# PhaseCLeg.net
KiCad netlist of a schematic drawn in Altium Designer
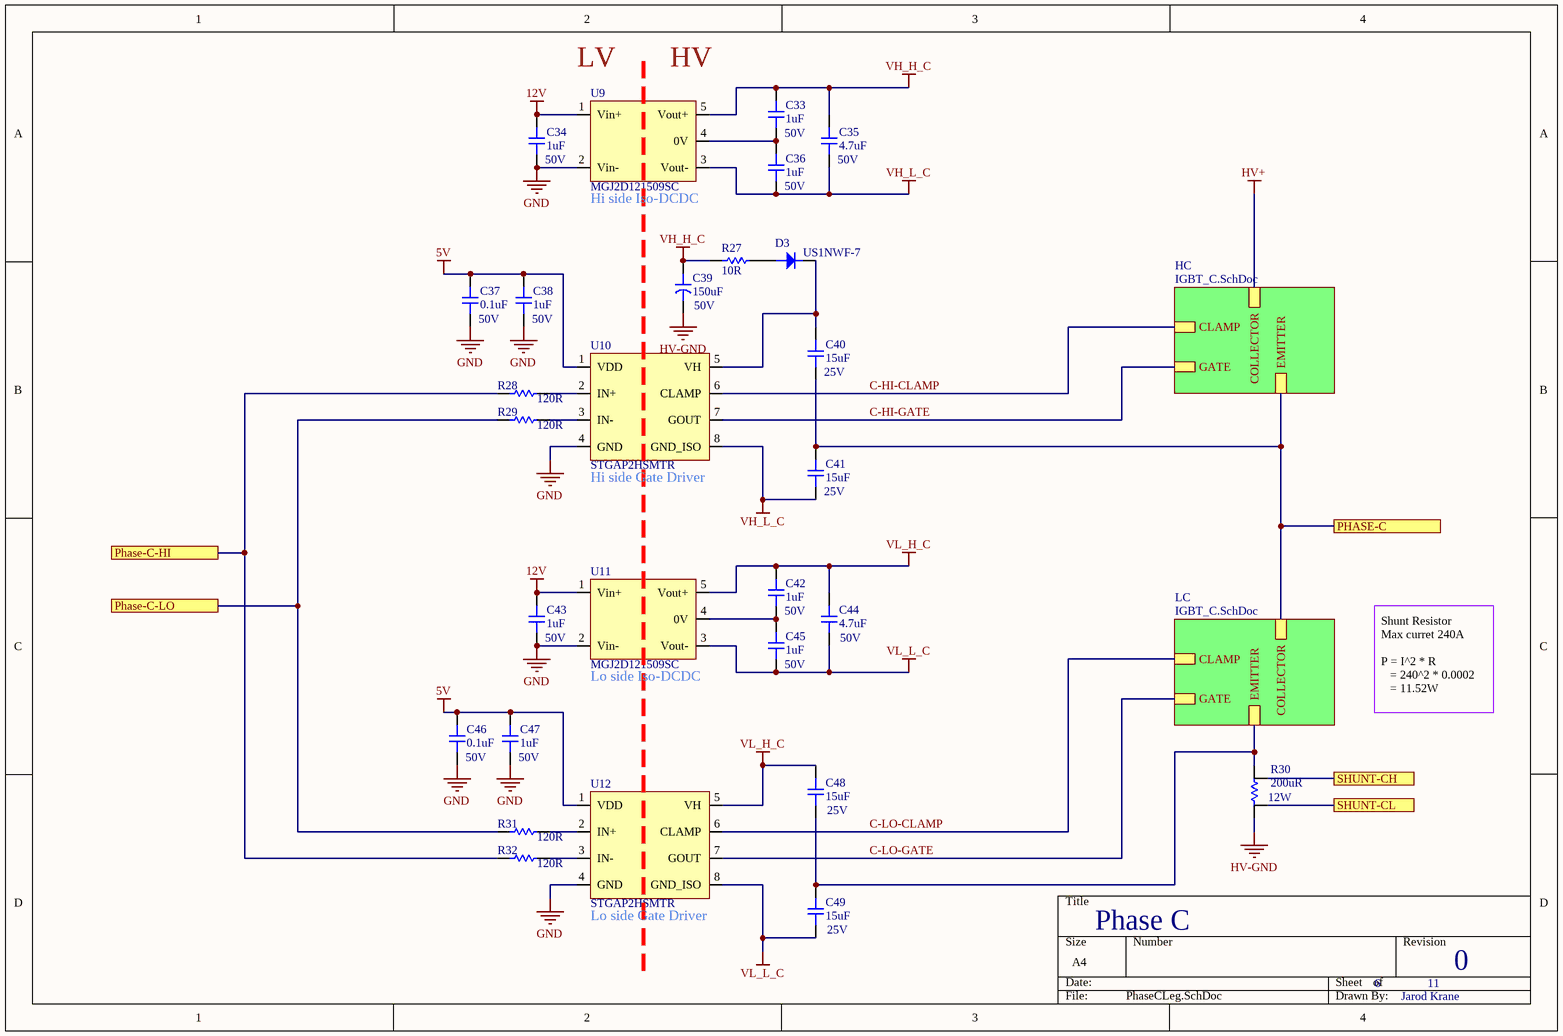
[diagram p0: PhaseCLeg.SchDoc]

(export (version "E")
  (design (tool "Eeschema 10.0.6"))
  (components
    (comp (ref "C33")
      (value "1uF")
      (footprint "CAP-0805")
      (description "CAP CER 1UF 50V X5R 0805")
      (fields
        (field (name "MANUFACTURER") "KEMET")
        (field (name "MANUFACTURER PART NUMBER") "C0805C105K5PACTU")
        (field (name "VOLTAGE RATING") "50V")
      )
      (libsource (lib "InverterSCHLib") (part "0805-1uF-50V"))
    )
    (comp (ref "C34")
      (value "1uF")
      (footprint "CAP-0805")
      (description "CAP CER 1UF 50V X5R 0805")
      (fields
        (field (name "MANUFACTURER") "KEMET")
        (field (name "MANUFACTURER PART NUMBER") "C0805C105K5PACTU")
        (field (name "VOLTAGE RATING") "50V")
      )
      (libsource (lib "InverterSCHLib") (part "0805-1uF-50V"))
    )
    (comp (ref "C35")
      (value "4.7uF")
      (footprint "CAP-1206")
      (description "CAP CER 4.7UF 50V X7R 1206")
      (fields
        (field (name "MANUFACTURER") "TDK")
        (field (name "MANUFACTURER PART NUMBER") "C3216X7R1H475K160AC")
        (field (name "VOLTAGE RATING") "50V")
      )
      (libsource (lib "InverterSCHLib") (part "1206-4.7uF-50V"))
    )
    (comp (ref "C36")
      (value "1uF")
      (footprint "CAP-0805")
      (description "CAP CER 1UF 50V X5R 0805")
      (fields
        (field (name "MANUFACTURER") "KEMET")
        (field (name "MANUFACTURER PART NUMBER") "C0805C105K5PACTU")
        (field (name "VOLTAGE RATING") "50V")
      )
      (libsource (lib "InverterSCHLib") (part "0805-1uF-50V"))
    )
    (comp (ref "C37")
      (value "0.1uF")
      (footprint "CAP-0805")
      (description "CAP CER 0.1UF 50V Y5V 0805")
      (fields
        (field (name "MANUFACTURER") "KEMET")
        (field (name "MANUFACTURER PART NUMBER") "C0805C104Z5VACTU")
        (field (name "VOLTAGE") "50V")
      )
      (libsource (lib "InverterSCHLib") (part "0805-0.1uF-50V"))
    )
    (comp (ref "C38")
      (value "1uF")
      (footprint "CAP-0805")
      (description "CAP CER 1UF 50V X5R 0805")
      (fields
        (field (name "MANUFACTURER") "KEMET")
        (field (name "MANUFACTURER PART NUMBER") "C0805C105K5PACTU")
        (field (name "VOLTAGE RATING") "50V")
      )
      (libsource (lib "InverterSCHLib") (part "0805-1uF-50V"))
    )
    (comp (ref "C39")
      (value "150uF")
      (footprint "CAPCAN-10mm")
      (description "CAP POLYMER HYBRID 150UF 50V SMD")
      (fields
        (field (name "MANUFACTURER") "Panasonic")
        (field (name "MANUFACTURER PART NUMBER") "EEHZS1H151P")
        (field (name "VOLTAGE") "50V")
      )
      (libsource (lib "InverterSCHLib") (part "10mm-150uF-50V"))
    )
    (comp (ref "C40")
      (value "15uF")
      (footprint "CAP-1812")
      (description "CAP CER 15UF 25V X7R 1812")
      (fields
        (field (name "MANUFACTURER") "TDK")
        (field (name "MANUFACTURER PART NUMBER") "C4532X7R1E156M280KB")
        (field (name "VOLTAGE") "25V")
      )
      (libsource (lib "InverterSCHLib") (part "1812-15uF-25V"))
    )
    (comp (ref "C41")
      (value "15uF")
      (footprint "CAP-1812")
      (description "CAP CER 15UF 25V X7R 1812")
      (fields
        (field (name "MANUFACTURER") "TDK")
        (field (name "MANUFACTURER PART NUMBER") "C4532X7R1E156M280KB")
        (field (name "VOLTAGE") "25V")
      )
      (libsource (lib "InverterSCHLib") (part "1812-15uF-25V"))
    )
    (comp (ref "C42")
      (value "1uF")
      (footprint "CAP-0805")
      (description "CAP CER 1UF 50V X5R 0805")
      (fields
        (field (name "MANUFACTURER") "KEMET")
        (field (name "MANUFACTURER PART NUMBER") "C0805C105K5PACTU")
        (field (name "VOLTAGE RATING") "50V")
      )
      (libsource (lib "InverterSCHLib") (part "0805-1uF-50V"))
    )
    (comp (ref "C43")
      (value "1uF")
      (footprint "CAP-0805")
      (description "CAP CER 1UF 50V X5R 0805")
      (fields
        (field (name "MANUFACTURER") "KEMET")
        (field (name "MANUFACTURER PART NUMBER") "C0805C105K5PACTU")
        (field (name "VOLTAGE RATING") "50V")
      )
      (libsource (lib "InverterSCHLib") (part "0805-1uF-50V"))
    )
    (comp (ref "C44")
      (value "4.7uF")
      (footprint "CAP-1206")
      (description "CAP CER 4.7UF 50V X7R 1206")
      (fields
        (field (name "MANUFACTURER") "TDK")
        (field (name "MANUFACTURER PART NUMBER") "C3216X7R1H475K160AC")
        (field (name "VOLTAGE RATING") "50V")
      )
      (libsource (lib "InverterSCHLib") (part "1206-4.7uF-50V"))
    )
    (comp (ref "C45")
      (value "1uF")
      (footprint "CAP-0805")
      (description "CAP CER 1UF 50V X5R 0805")
      (fields
        (field (name "MANUFACTURER") "KEMET")
        (field (name "MANUFACTURER PART NUMBER") "C0805C105K5PACTU")
        (field (name "VOLTAGE RATING") "50V")
      )
      (libsource (lib "InverterSCHLib") (part "0805-1uF-50V"))
    )
    (comp (ref "C46")
      (value "0.1uF")
      (footprint "CAP-0805")
      (description "CAP CER 0.1UF 50V Y5V 0805")
      (fields
        (field (name "MANUFACTURER") "KEMET")
        (field (name "MANUFACTURER PART NUMBER") "C0805C104Z5VACTU")
        (field (name "VOLTAGE") "50V")
      )
      (libsource (lib "InverterSCHLib") (part "0805-0.1uF-50V"))
    )
    (comp (ref "C47")
      (value "1uF")
      (footprint "CAP-0805")
      (description "CAP CER 1UF 50V X5R 0805")
      (fields
        (field (name "MANUFACTURER") "KEMET")
        (field (name "MANUFACTURER PART NUMBER") "C0805C105K5PACTU")
        (field (name "VOLTAGE RATING") "50V")
      )
      (libsource (lib "InverterSCHLib") (part "0805-1uF-50V"))
    )
    (comp (ref "C48")
      (value "15uF")
      (footprint "CAP-1812")
      (description "CAP CER 15UF 25V X7R 1812")
      (fields
        (field (name "MANUFACTURER") "TDK")
        (field (name "MANUFACTURER PART NUMBER") "C4532X7R1E156M280KB")
        (field (name "VOLTAGE") "25V")
      )
      (libsource (lib "InverterSCHLib") (part "1812-15uF-25V"))
    )
    (comp (ref "C49")
      (value "15uF")
      (footprint "CAP-1812")
      (description "CAP CER 15UF 25V X7R 1812")
      (fields
        (field (name "MANUFACTURER") "TDK")
        (field (name "MANUFACTURER PART NUMBER") "C4532X7R1E156M280KB")
        (field (name "VOLTAGE") "25V")
      )
      (libsource (lib "InverterSCHLib") (part "1812-15uF-25V"))
    )
    (comp (ref "D3")
      (value "US1NWF-7")
      (footprint "DIOM2718X12N")
      (description "DIODE GEN PURP 1.2KV 1A SOD123F")
      (fields (field (name "MANUFACTURER") "Diodes"))
      (libsource (lib "InverterSCHLib") (part "Diode 1.2KV-1A"))
    )
    (comp (ref "R27")
      (value "10R")
      (footprint "RES-0603")
      (description "RES SMD 10 OHM 1% 1/10W 0603")
      (fields
        (field (name "MANUFACTURER") "Yageo")
        (field (name "MANUFACTURER PART NUMBER") "RC0603FR-0710RL")
      )
      (libsource (lib "InverterSCHLib") (part "0603-10R"))
    )
    (comp (ref "R28")
      (value "120R")
      (footprint "RES-0603")
      (description "RES SMD 120 OHM 1% 1/10W 0603")
      (fields
        (field (name "MANUFACTURER") "Yageo")
        (field (name "MANUFACTURER PART NUMBER") "RC0603FR-07120RL")
      )
      (libsource (lib "InverterSCHLib") (part "0603-120R"))
    )
    (comp (ref "R29")
      (value "120R")
      (footprint "RES-0603")
      (description "RES SMD 120 OHM 1% 1/10W 0603")
      (fields
        (field (name "MANUFACTURER") "Yageo")
        (field (name "MANUFACTURER PART NUMBER") "RC0603FR-07120RL")
      )
      (libsource (lib "InverterSCHLib") (part "0603-120R"))
    )
    (comp (ref "R30")
      (value "200uR")
      (footprint "RES-SHUNT")
      (description "RES SMD 200 UOHM 1% 12W 3920")
      (fields
        (field (name "MANUFACTURER") "Bourns")
        (field (name "MANUFACTURER PART NUMBER") "CSS2H-3920R-L200FE")
        (field (name "POWER") "12W")
      )
      (libsource (lib "InverterSCHLib") (part "3920-200uR-SHUNT"))
    )
    (comp (ref "R31")
      (value "120R")
      (footprint "RES-0603")
      (description "RES SMD 120 OHM 1% 1/10W 0603")
      (fields
        (field (name "MANUFACTURER") "Yageo")
        (field (name "MANUFACTURER PART NUMBER") "RC0603FR-07120RL")
      )
      (libsource (lib "InverterSCHLib") (part "0603-120R"))
    )
    (comp (ref "R32")
      (value "120R")
      (footprint "RES-0603")
      (description "RES SMD 120 OHM 1% 1/10W 0603")
      (fields
        (field (name "MANUFACTURER") "Yageo")
        (field (name "MANUFACTURER PART NUMBER") "RC0603FR-07120RL")
      )
      (libsource (lib "InverterSCHLib") (part "0603-120R"))
    )
    (comp (ref "U9")
      (value "MGJ2D121509SC")
      (footprint "MGJ2")
      (description "Isolated Module DC DC Converter Output 15V -8.7V - 80mA, 40mA 10.8V - 13.2V Input")
      (fields (field (name "MANUFACTURER") "Murata"))
      (libsource (lib "InverterSCHLib") (part "15V/-8.7V"))
    )
    (comp (ref "U10")
      (value "STGAP2HSMTR")
      (footprint "SO-8W")
      (description "GALVANICALLY ISOLATED 4 A SINGLE GATE DRIVER")
      (fields
        (field (name "MANUFACTURER") "Samtec")
        (field (name "MANUFACTURER PART NUMBER") "ERF8-010-07.0-L-DV-L-K-TR")
      )
      (libsource (lib "InverterSCHLib") (part "STGAP2HSMTR"))
    )
    (comp (ref "U11")
      (value "MGJ2D121509SC")
      (footprint "MGJ2")
      (description "Isolated Module DC DC Converter Output 15V -8.7V - 80mA, 40mA 10.8V - 13.2V Input")
      (fields (field (name "MANUFACTURER") "Murata"))
      (libsource (lib "InverterSCHLib") (part "15V/-8.7V"))
    )
    (comp (ref "U12")
      (value "STGAP2HSMTR")
      (footprint "SO-8W")
      (description "GALVANICALLY ISOLATED 4 A SINGLE GATE DRIVER")
      (fields
        (field (name "MANUFACTURER") "Samtec")
        (field (name "MANUFACTURER PART NUMBER") "ERF8-010-07.0-L-DV-L-K-TR")
      )
      (libsource (lib "InverterSCHLib") (part "STGAP2HSMTR"))
    )
  )
  (nets
    (net (code "1") (name "/C-HI-CLAMP") (class "Default")
      (node (ref "U10") (pin "6") (pinfunction "CLAMP_6") (pintype "passive"))
    )
    (net (code "2") (name "/C-HI-GATE") (class "Default")
      (node (ref "U10") (pin "7") (pinfunction "GOUT_7") (pintype "passive"))
    )
    (net (code "3") (name "/C-LO-CLAMP") (class "Default")
      (node (ref "U12") (pin "6") (pinfunction "CLAMP_6") (pintype "passive"))
    )
    (net (code "4") (name "/C-LO-GATE") (class "Default")
      (node (ref "U12") (pin "7") (pinfunction "GOUT_7") (pintype "passive"))
    )
    (net (code "5") (name "/EMITTER") (class "Default")
      (node (ref "C48") (pin "1") (pinfunction "1_1") (pintype "passive"))
      (node (ref "C49") (pin "2") (pinfunction "2_2") (pintype "passive"))
      (node (ref "R30") (pin "2") (pinfunction "2_2") (pintype "passive"))
    )
    (net (code "6") (name "/PHASE-C") (class "Default")
      (node (ref "C40") (pin "1") (pinfunction "1_1") (pintype "passive"))
      (node (ref "C41") (pin "2") (pinfunction "2_2") (pintype "passive"))
    )
    (net (code "7") (name "/Phase-C-HI") (class "Default")
      (node (ref "R28") (pin "1") (pinfunction "1_1") (pintype "passive"))
      (node (ref "R32") (pin "1") (pinfunction "1_1") (pintype "passive"))
    )
    (net (code "8") (name "/Phase-C-LO") (class "Default")
      (node (ref "R29") (pin "1") (pinfunction "1_1") (pintype "passive"))
      (node (ref "R31") (pin "1") (pinfunction "1_1") (pintype "passive"))
    )
    (net (code "9") (name "/SHUNT-CH") (class "Default")
      (node (ref "R30") (pin "4") (pinfunction "4_4") (pintype "passive"))
    )
    (net (code "10") (name "/SHUNT-CL") (class "Default")
      (node (ref "R30") (pin "3") (pinfunction "3_3") (pintype "passive"))
    )
    (net (code "11") (name "5V") (class "Default")
      (node (ref "C37") (pin "2") (pinfunction "2_2") (pintype "passive"))
      (node (ref "C38") (pin "2") (pinfunction "2_2") (pintype "passive"))
      (node (ref "C46") (pin "2") (pinfunction "2_2") (pintype "passive"))
      (node (ref "C47") (pin "2") (pinfunction "2_2") (pintype "passive"))
      (node (ref "U10") (pin "1") (pinfunction "VDD_1") (pintype "passive"))
      (node (ref "U12") (pin "1") (pinfunction "VDD_1") (pintype "passive"))
    )
    (net (code "12") (name "12V") (class "Default")
      (node (ref "C34") (pin "2") (pinfunction "2_2") (pintype "passive"))
      (node (ref "C43") (pin "2") (pinfunction "2_2") (pintype "passive"))
      (node (ref "U11") (pin "1") (pinfunction "Vin+_1") (pintype "passive"))
      (node (ref "U9") (pin "1") (pinfunction "Vin+_1") (pintype "passive"))
    )
    (net (code "13") (name "GND") (class "Default")
      (node (ref "C34") (pin "1") (pinfunction "1_1") (pintype "passive"))
      (node (ref "C37") (pin "1") (pinfunction "1_1") (pintype "passive"))
      (node (ref "C38") (pin "1") (pinfunction "1_1") (pintype "passive"))
      (node (ref "C43") (pin "1") (pinfunction "1_1") (pintype "passive"))
      (node (ref "C46") (pin "1") (pinfunction "1_1") (pintype "passive"))
      (node (ref "C47") (pin "1") (pinfunction "1_1") (pintype "passive"))
      (node (ref "U10") (pin "4") (pinfunction "GND_4") (pintype "passive"))
      (node (ref "U11") (pin "2") (pinfunction "Vin-_2") (pintype "passive"))
      (node (ref "U12") (pin "4") (pinfunction "GND_4") (pintype "passive"))
      (node (ref "U9") (pin "2") (pinfunction "Vin-_2") (pintype "passive"))
    )
    (net (code "15") (name "HV-GND") (class "Default")
      (node (ref "C39") (pin "2") (pinfunction "2_2") (pintype "passive"))
      (node (ref "R30") (pin "1") (pinfunction "1_1") (pintype "passive"))
    )
    (net (code "16") (name "Net-(D3-Pad2)") (class "Default")
      (node (ref "D3") (pin "2") (pinfunction "2_2") (pintype "passive"))
      (node (ref "R27") (pin "2") (pinfunction "2_2") (pintype "passive"))
    )
    (net (code "17") (name "Net-(U9-0V)") (class "Default")
      (node (ref "C33") (pin "1") (pinfunction "1_1") (pintype "passive"))
      (node (ref "C36") (pin "2") (pinfunction "2_2") (pintype "passive"))
      (node (ref "U9") (pin "4") (pinfunction "0V_4") (pintype "passive"))
    )
    (net (code "18") (name "Net-(U10-IN+)") (class "Default")
      (node (ref "R28") (pin "2") (pinfunction "2_2") (pintype "passive"))
      (node (ref "U10") (pin "2") (pinfunction "IN+_2") (pintype "passive"))
    )
    (net (code "19") (name "Net-(U10-IN-)") (class "Default")
      (node (ref "R29") (pin "2") (pinfunction "2_2") (pintype "passive"))
      (node (ref "U10") (pin "3") (pinfunction "IN-_3") (pintype "passive"))
    )
    (net (code "20") (name "Net-(U10-VH)") (class "Default")
      (node (ref "C40") (pin "2") (pinfunction "2_2") (pintype "passive"))
      (node (ref "D3") (pin "1") (pinfunction "1_1") (pintype "passive"))
      (node (ref "U10") (pin "5") (pinfunction "VH_5") (pintype "passive"))
    )
    (net (code "21") (name "Net-(U11-0V)") (class "Default")
      (node (ref "C42") (pin "1") (pinfunction "1_1") (pintype "passive"))
      (node (ref "C45") (pin "2") (pinfunction "2_2") (pintype "passive"))
      (node (ref "U11") (pin "4") (pinfunction "0V_4") (pintype "passive"))
    )
    (net (code "22") (name "Net-(U12-IN+)") (class "Default")
      (node (ref "R31") (pin "2") (pinfunction "2_2") (pintype "passive"))
      (node (ref "U12") (pin "2") (pinfunction "IN+_2") (pintype "passive"))
    )
    (net (code "23") (name "Net-(U12-IN-)") (class "Default")
      (node (ref "R32") (pin "2") (pinfunction "2_2") (pintype "passive"))
      (node (ref "U12") (pin "3") (pinfunction "IN-_3") (pintype "passive"))
    )
    (net (code "24") (name "VH_H_C") (class "Default")
      (node (ref "C33") (pin "2") (pinfunction "2_2") (pintype "passive"))
      (node (ref "C35") (pin "2") (pinfunction "2_2") (pintype "passive"))
      (node (ref "C39") (pin "1") (pinfunction "1_1") (pintype "passive"))
      (node (ref "R27") (pin "1") (pinfunction "1_1") (pintype "passive"))
      (node (ref "U9") (pin "5") (pinfunction "Vout+_5") (pintype "passive"))
    )
    (net (code "25") (name "VH_L_C") (class "Default")
      (node (ref "C35") (pin "1") (pinfunction "1_1") (pintype "passive"))
      (node (ref "C36") (pin "1") (pinfunction "1_1") (pintype "passive"))
      (node (ref "C41") (pin "1") (pinfunction "1_1") (pintype "passive"))
      (node (ref "U10") (pin "8") (pinfunction "GND_ISO_8") (pintype "passive"))
      (node (ref "U9") (pin "3") (pinfunction "Vout-_3") (pintype "passive"))
    )
    (net (code "26") (name "VL_H_C") (class "Default")
      (node (ref "C42") (pin "2") (pinfunction "2_2") (pintype "passive"))
      (node (ref "C44") (pin "2") (pinfunction "2_2") (pintype "passive"))
      (node (ref "C48") (pin "2") (pinfunction "2_2") (pintype "passive"))
      (node (ref "U11") (pin "5") (pinfunction "Vout+_5") (pintype "passive"))
      (node (ref "U12") (pin "5") (pinfunction "VH_5") (pintype "passive"))
    )
    (net (code "27") (name "VL_L_C") (class "Default")
      (node (ref "C44") (pin "1") (pinfunction "1_1") (pintype "passive"))
      (node (ref "C45") (pin "1") (pinfunction "1_1") (pintype "passive"))
      (node (ref "C49") (pin "1") (pinfunction "1_1") (pintype "passive"))
      (node (ref "U11") (pin "3") (pinfunction "Vout-_3") (pintype "passive"))
      (node (ref "U12") (pin "8") (pinfunction "GND_ISO_8") (pintype "passive"))
    )
  )
)
